# EMG_PCB_Open-source.net
KiCad netlist of a schematic drawn in EAGLE
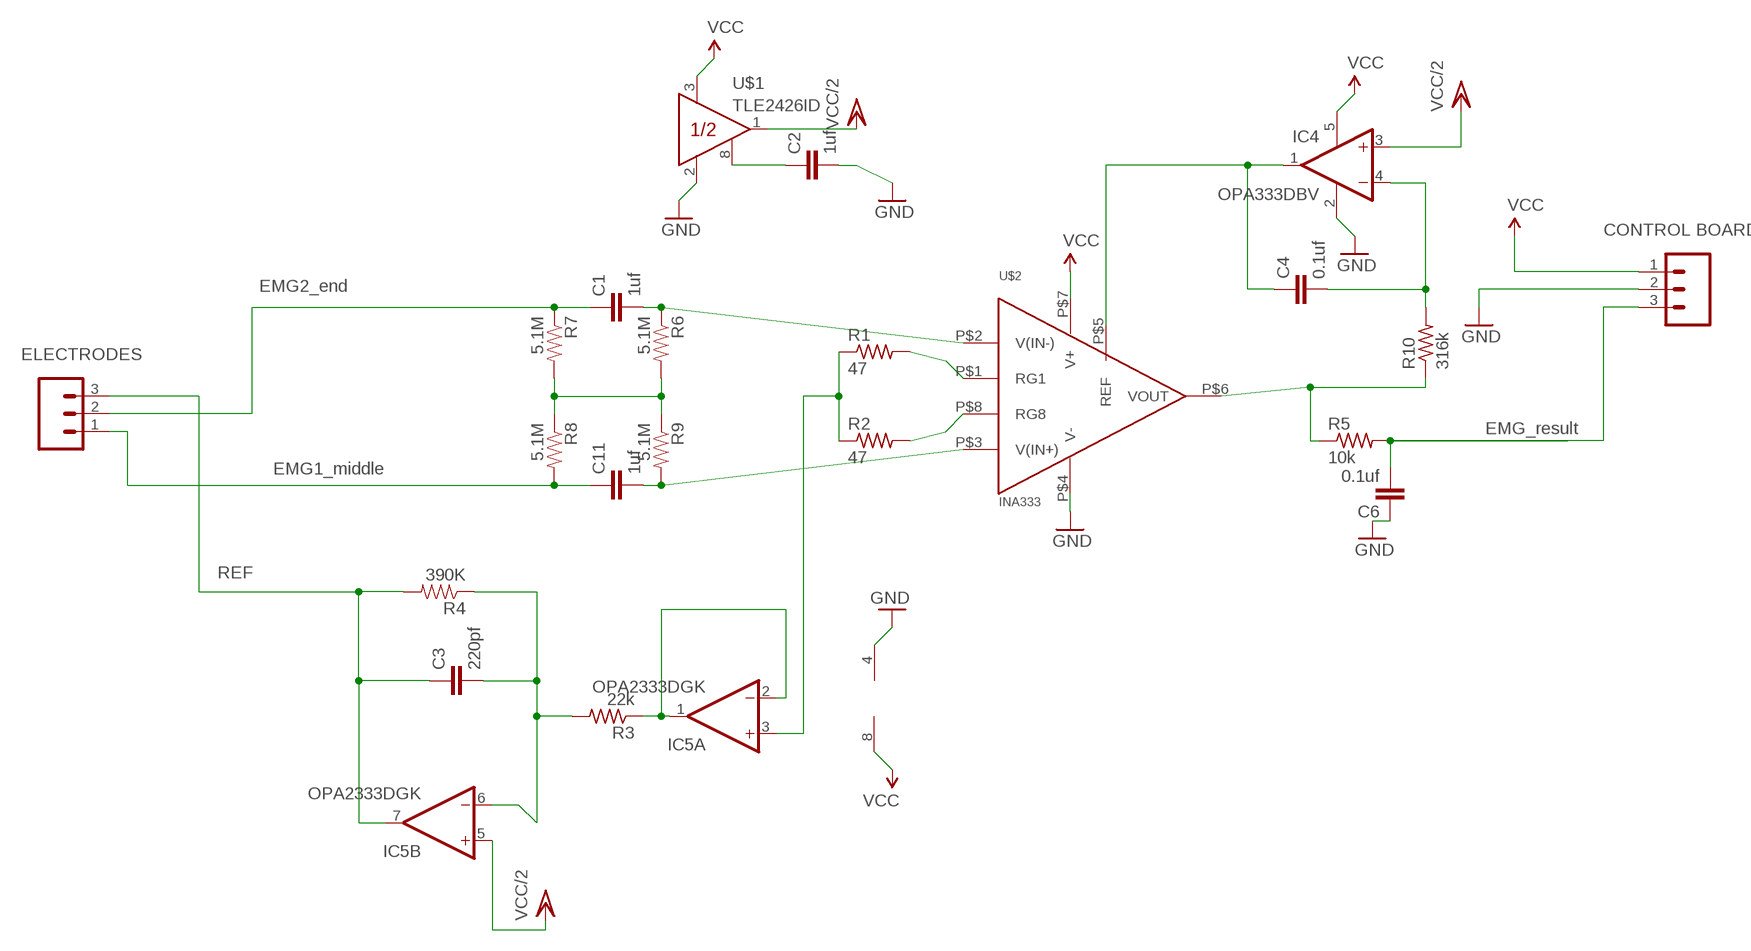
[diagram p0: schematic, sheet 1]

(export (version "E")
  (design (tool "Eeschema 10.0.6"))
  (components
    (comp (ref "C1")
      (value "1uf")
      (footprint "eagle-import:C0603")
      (libsource (lib "eagle-import") (part "C-EUC0603"))
    )
    (comp (ref "C2")
      (value "1uf")
      (footprint "eagle-import:C0603")
      (libsource (lib "eagle-import") (part "C-EUC0603"))
    )
    (comp (ref "C3")
      (value "220pf")
      (footprint "eagle-import:C0603")
      (libsource (lib "eagle-import") (part "C-EUC0603"))
    )
    (comp (ref "C4")
      (value "0.1uf")
      (footprint "eagle-import:C0603")
      (libsource (lib "eagle-import") (part "C-EUC0603"))
    )
    (comp (ref "C6")
      (value "0.1uf")
      (footprint "eagle-import:C0603")
      (libsource (lib "eagle-import") (part "C-EUC0603"))
    )
    (comp (ref "C11")
      (value "1uf")
      (footprint "eagle-import:C0603")
      (libsource (lib "eagle-import") (part "C-EUC0603"))
    )
    (comp (ref "IC4")
      (value "OPA333DBV")
      (footprint "eagle-import:SOT23-5")
      (libsource (lib "eagle-import") (part "OPA333DBV"))
    )
    (comp (ref "IC5")
      (value "OPA2333DGK")
      (footprint "eagle-import:MSOP08")
      (libsource (lib "eagle-import") (part "OPA2333DGK"))
    )
    (comp (ref "J1")
      (value "455-1750-1-ND")
      (footprint "eagle-import:1X03")
      (libsource (lib "eagle-import") (part "CONN_03"))
    )
    (comp (ref "J2")
      (value "455-1750-1-ND")
      (footprint "eagle-import:1X03")
      (libsource (lib "eagle-import") (part "CONN_03"))
    )
    (comp (ref "R1")
      (value "47")
      (footprint "eagle-import:R0603")
      (libsource (lib "eagle-import") (part "R-US_R0603"))
    )
    (comp (ref "R2")
      (value "47")
      (footprint "eagle-import:R0603")
      (libsource (lib "eagle-import") (part "R-US_R0603"))
    )
    (comp (ref "R3")
      (value "22k")
      (footprint "eagle-import:R0603")
      (libsource (lib "eagle-import") (part "R-US_R0603"))
    )
    (comp (ref "R4")
      (value "390K")
      (footprint "eagle-import:0603-RES")
      (libsource (lib "eagle-import") (part "RESISTOR0603-RES"))
    )
    (comp (ref "R5")
      (value "10k")
      (footprint "eagle-import:R0603")
      (libsource (lib "eagle-import") (part "R-US_R0603"))
    )
    (comp (ref "R6")
      (value "5.1M")
      (footprint "eagle-import:0603-RES")
      (libsource (lib "eagle-import") (part "RESISTOR0603-RES"))
    )
    (comp (ref "R7")
      (value "5.1M")
      (footprint "eagle-import:0603-RES")
      (libsource (lib "eagle-import") (part "RESISTOR0603-RES"))
    )
    (comp (ref "R8")
      (value "5.1M")
      (footprint "eagle-import:0603-RES")
      (libsource (lib "eagle-import") (part "RESISTOR0603-RES"))
    )
    (comp (ref "R9")
      (value "5.1M")
      (footprint "eagle-import:0603-RES")
      (libsource (lib "eagle-import") (part "RESISTOR0603-RES"))
    )
    (comp (ref "R10")
      (value "316k")
      (footprint "eagle-import:R0603")
      (libsource (lib "eagle-import") (part "R-US_R0603"))
    )
    (comp (ref "U$1")
      (value "TLE2426ID")
      (footprint "eagle-import:SO-8")
      (libsource (lib "eagle-import") (part "TLE2426DI"))
    )
    (comp (ref "U$2")
      (value "INA333")
      (footprint "eagle-import:8-MSOP")
      (libsource (lib "eagle-import") (part "INA333"))
    )
  )
  (nets
    (net (code "1") (name "GND") (class "Default")
      (node (ref "C2") (pin "2") (pinfunction "2_2") (pintype "passive"))
      (node (ref "C6") (pin "1") (pinfunction "1_1") (pintype "passive"))
      (node (ref "IC4") (pin "2") (pinfunction "V-_2") (pintype "power_in"))
      (node (ref "IC5") (pin "4") (pinfunction "V-_4") (pintype "power_in"))
      (node (ref "J2") (pin "2") (pinfunction "2_2") (pintype "passive"))
      (node (ref "U$1") (pin "2") (pinfunction "COM_2") (pintype "passive"))
      (node (ref "U$2") (pin "P$4") (pinfunction "V-_P$4") (pintype "bidirectional"))
    )
    (net (code "2") (name "Net-(C1-Pad1)") (class "Default")
      (node (ref "C1") (pin "1") (pinfunction "1_1") (pintype "passive"))
      (node (ref "J1") (pin "2") (pinfunction "2_2") (pintype "passive"))
      (node (ref "R7") (pin "1") (pinfunction "1_1") (pintype "passive"))
    )
    (net (code "3") (name "Net-(C6-Pad2)") (class "Default")
      (node (ref "C6") (pin "2") (pinfunction "2_2") (pintype "passive"))
      (node (ref "J2") (pin "3") (pinfunction "3_3") (pintype "passive"))
      (node (ref "R5") (pin "2") (pinfunction "2_2") (pintype "passive"))
    )
    (net (code "4") (name "Net-(C11-Pad1)") (class "Default")
      (node (ref "C11") (pin "1") (pinfunction "1_1") (pintype "passive"))
      (node (ref "J1") (pin "1") (pinfunction "1_1") (pintype "passive"))
      (node (ref "R8") (pin "2") (pinfunction "2_2") (pintype "passive"))
    )
    (net (code "5") (name "Net-(IC4--IN)") (class "Default")
      (node (ref "C4") (pin "2") (pinfunction "2_2") (pintype "passive"))
      (node (ref "IC4") (pin "4") (pinfunction "-IN_4") (pintype "input"))
      (node (ref "R10") (pin "2") (pinfunction "2_2") (pintype "passive"))
    )
    (net (code "6") (name "Net-(IC4-OUT)") (class "Default")
      (node (ref "C4") (pin "1") (pinfunction "1_1") (pintype "passive"))
      (node (ref "IC4") (pin "1") (pinfunction "OUT_1") (pintype "output"))
      (node (ref "U$2") (pin "P$5") (pinfunction "REF_P$5") (pintype "bidirectional"))
    )
    (net (code "7") (name "Net-(IC5A-+IN)") (class "Default")
      (node (ref "IC5") (pin "3") (pinfunction "+IN_3") (pintype "input"))
      (node (ref "R1") (pin "1") (pinfunction "1_1") (pintype "passive"))
      (node (ref "R2") (pin "1") (pinfunction "1_1") (pintype "passive"))
    )
    (net (code "8") (name "Net-(IC5A--IN)") (class "Default")
      (node (ref "IC5") (pin "1") (pinfunction "OUT_1") (pintype "output"))
      (node (ref "IC5") (pin "2") (pinfunction "-IN_2") (pintype "input"))
      (node (ref "R3") (pin "1") (pinfunction "1_1") (pintype "passive"))
    )
    (net (code "9") (name "Net-(IC5B--IN)") (class "Default")
      (node (ref "C3") (pin "2") (pinfunction "2_2") (pintype "passive"))
      (node (ref "IC5") (pin "6") (pinfunction "-IN_6") (pintype "input"))
      (node (ref "R3") (pin "2") (pinfunction "2_2") (pintype "passive"))
      (node (ref "R4") (pin "1") (pinfunction "1_1") (pintype "passive"))
    )
    (net (code "10") (name "Net-(IC5B-OUT)") (class "Default")
      (node (ref "C3") (pin "1") (pinfunction "1_1") (pintype "passive"))
      (node (ref "IC5") (pin "7") (pinfunction "OUT_7") (pintype "output"))
      (node (ref "J1") (pin "3") (pinfunction "3_3") (pintype "passive"))
      (node (ref "R4") (pin "2") (pinfunction "2_2") (pintype "passive"))
    )
    (net (code "11") (name "Net-(R6-Pad2)") (class "Default")
      (node (ref "R6") (pin "2") (pinfunction "2_2") (pintype "passive"))
      (node (ref "R7") (pin "2") (pinfunction "2_2") (pintype "passive"))
      (node (ref "R8") (pin "1") (pinfunction "1_1") (pintype "passive"))
      (node (ref "R9") (pin "1") (pinfunction "1_1") (pintype "passive"))
    )
    (net (code "12") (name "Net-(U$1-NR)") (class "Default")
      (node (ref "C2") (pin "1") (pinfunction "1_1") (pintype "passive"))
      (node (ref "U$1") (pin "8") (pinfunction "NR_8") (pintype "passive"))
    )
    (net (code "13") (name "Net-(U$2-RG1)") (class "Default")
      (node (ref "R1") (pin "2") (pinfunction "2_2") (pintype "passive"))
      (node (ref "U$2") (pin "P$1") (pinfunction "RG1_P$1") (pintype "bidirectional"))
    )
    (net (code "14") (name "Net-(U$2-RG8)") (class "Default")
      (node (ref "R2") (pin "2") (pinfunction "2_2") (pintype "passive"))
      (node (ref "U$2") (pin "P$8") (pinfunction "RG8_P$8") (pintype "bidirectional"))
    )
    (net (code "15") (name "Net-(U$2-V(IN+))") (class "Default")
      (node (ref "C11") (pin "2") (pinfunction "2_2") (pintype "passive"))
      (node (ref "R9") (pin "2") (pinfunction "2_2") (pintype "passive"))
      (node (ref "U$2") (pin "P$3") (pinfunction "V(IN+)_P$3") (pintype "bidirectional"))
    )
    (net (code "16") (name "Net-(U$2-V(IN-))") (class "Default")
      (node (ref "C1") (pin "2") (pinfunction "2_2") (pintype "passive"))
      (node (ref "R6") (pin "1") (pinfunction "1_1") (pintype "passive"))
      (node (ref "U$2") (pin "P$2") (pinfunction "V(IN-)_P$2") (pintype "bidirectional"))
    )
    (net (code "17") (name "Net-(U$2-VOUT)") (class "Default")
      (node (ref "R10") (pin "1") (pinfunction "1_1") (pintype "passive"))
      (node (ref "R5") (pin "1") (pinfunction "1_1") (pintype "passive"))
      (node (ref "U$2") (pin "P$6") (pinfunction "VOUT_P$6") (pintype "bidirectional"))
    )
    (net (code "18") (name "VCC") (class "Default")
      (node (ref "IC4") (pin "5") (pinfunction "V+_5") (pintype "power_in"))
      (node (ref "IC5") (pin "8") (pinfunction "V+_8") (pintype "power_in"))
      (node (ref "J2") (pin "1") (pinfunction "1_1") (pintype "passive"))
      (node (ref "U$1") (pin "3") (pinfunction "IN_3") (pintype "passive"))
      (node (ref "U$2") (pin "P$7") (pinfunction "V+_P$7") (pintype "bidirectional"))
    )
    (net (code "19") (name "VCC{slash}2") (class "Default")
      (node (ref "IC4") (pin "3") (pinfunction "+IN_3") (pintype "input"))
      (node (ref "IC5") (pin "5") (pinfunction "+IN_5") (pintype "input"))
      (node (ref "U$1") (pin "1") (pinfunction "OUT_1") (pintype "passive"))
    )
  )
)
